# p1_apfc_and_standby.net
KiCad netlist of a schematic drawn in Altium Designer
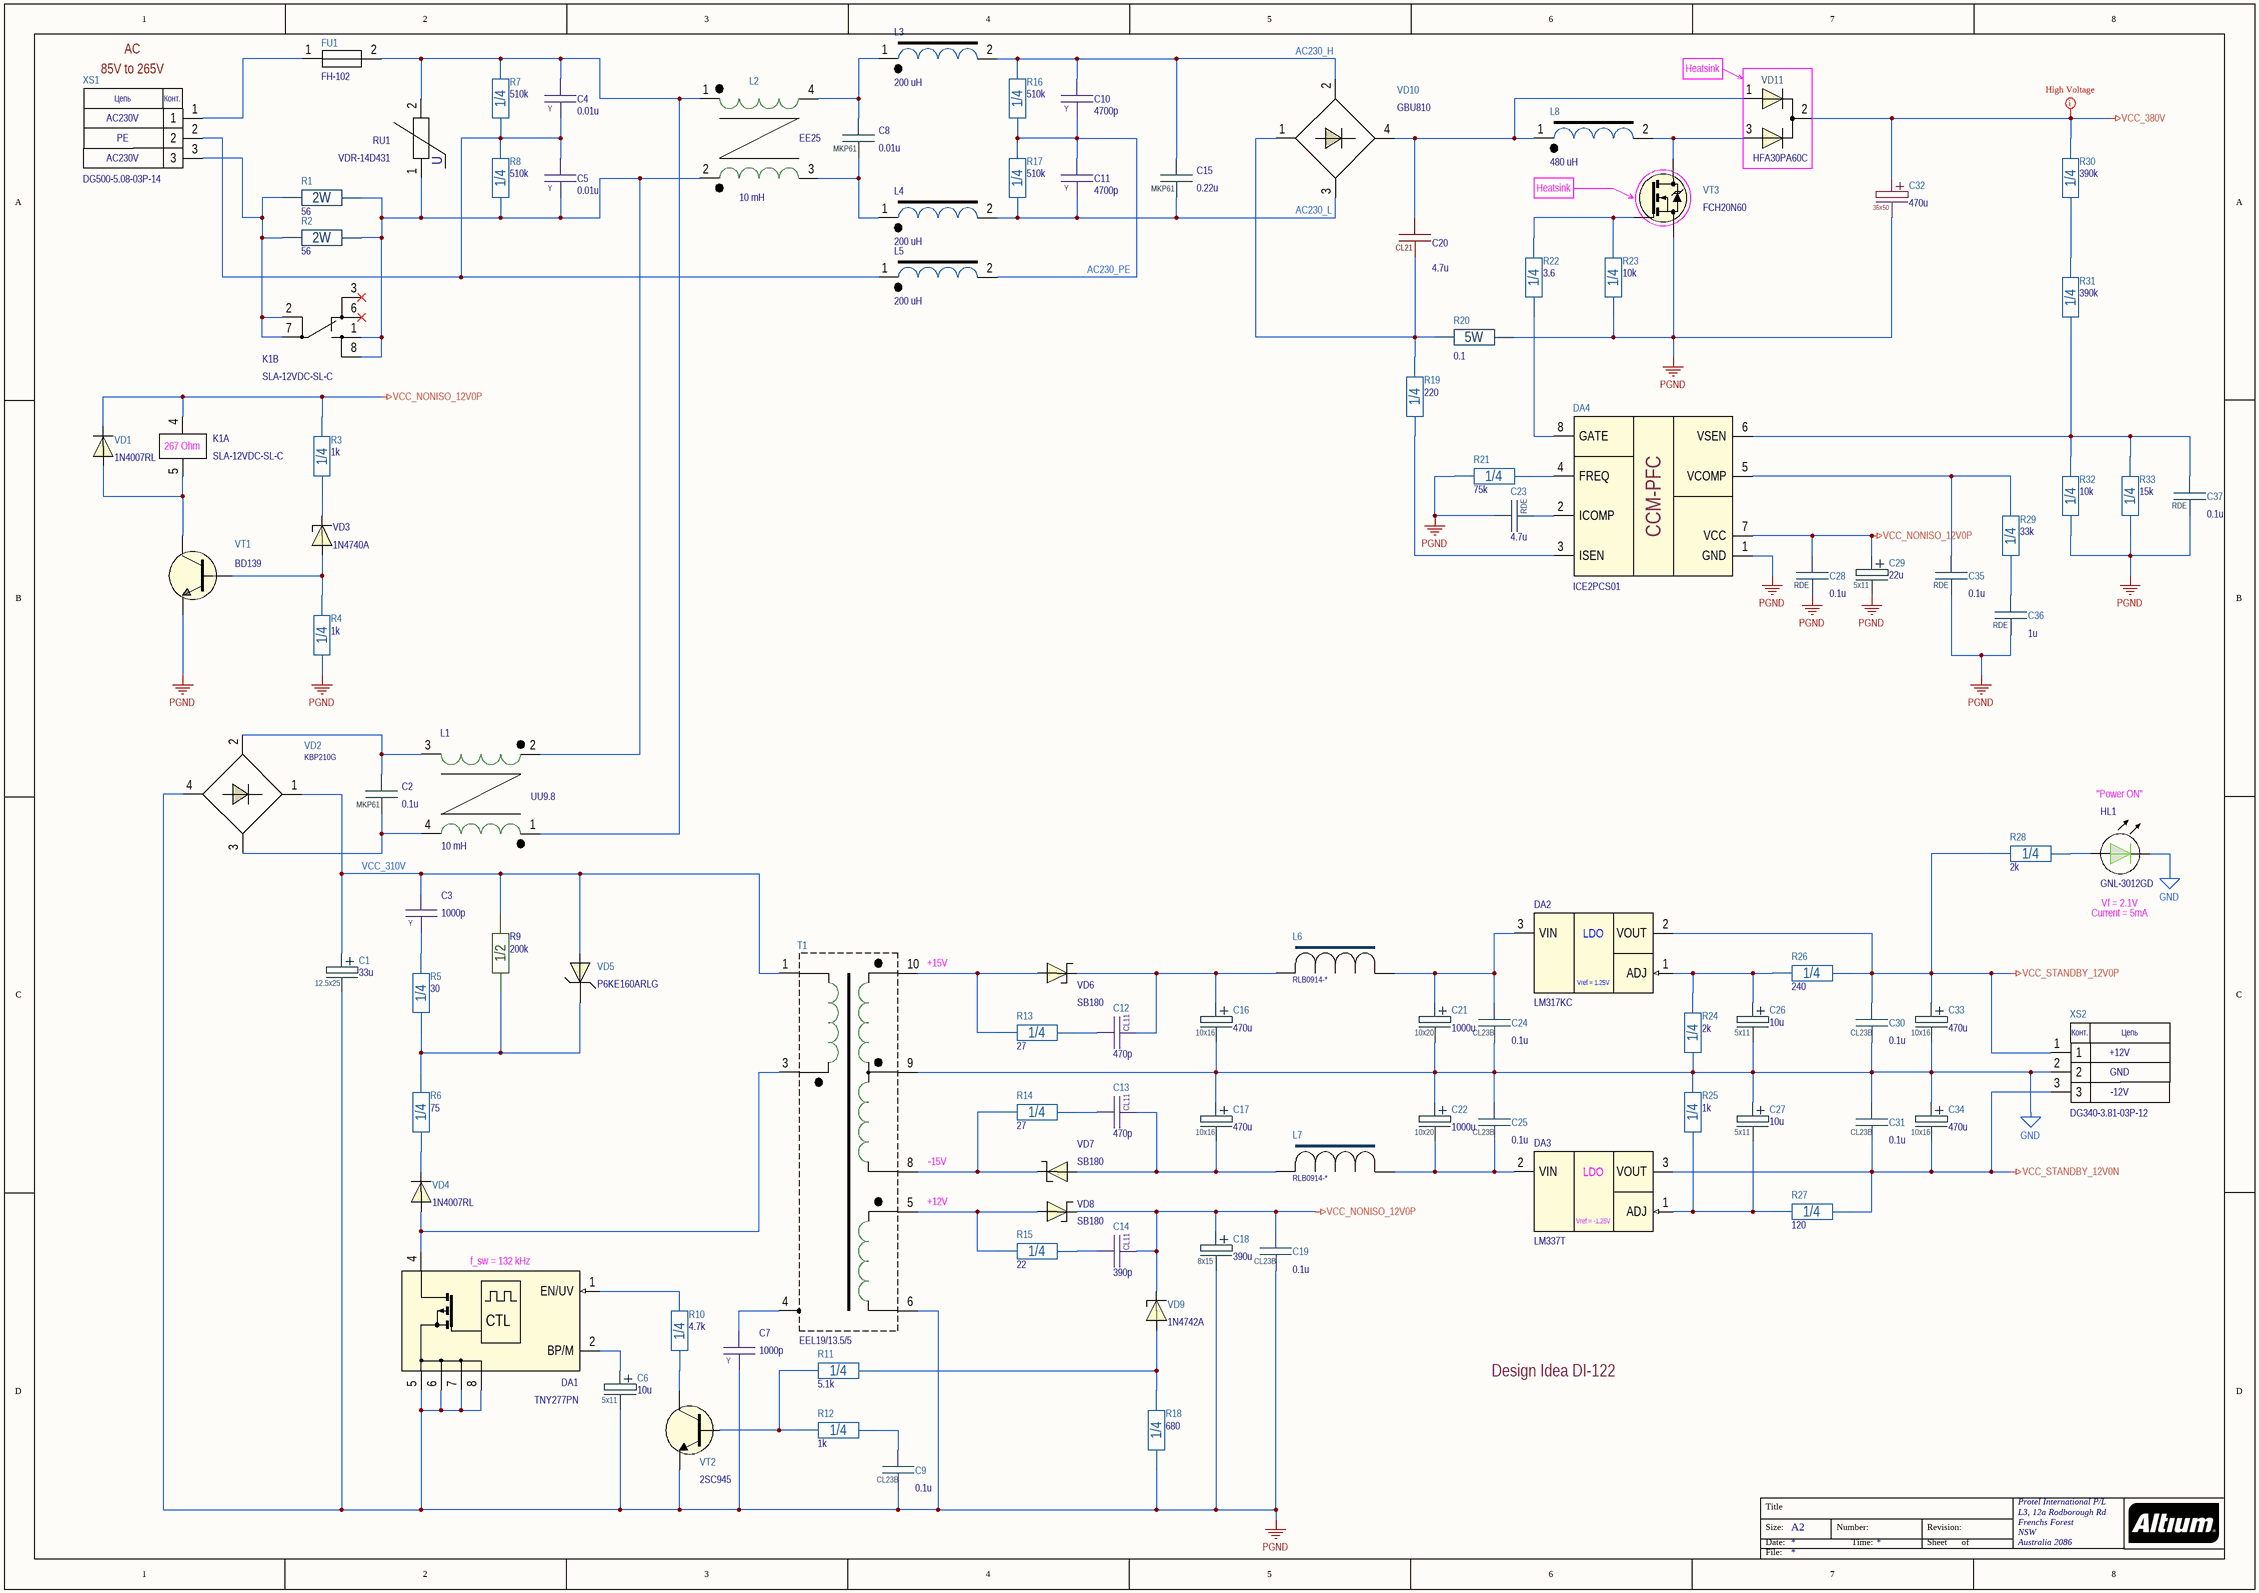
[diagram p0: p1_apfc_and_standby.SchDoc]

(export (version "E")
  (design (tool "Eeschema 10.0.6"))
  (components
    (comp (ref "C1")
      (value "33u")
      (footprint "PcbLib_RC:ECAP13X21X5_BRW")
      (description "Aluminium capacitor")
      (fields
        (field (name "TOLERANCE") "± 20 %")
        (field (name "VOLTAGE") "400V")
        (field (name "PACKAGE") "12.5x25")
      )
      (libsource (lib "Schlib_RC") (part "C_ECAP"))
    )
    (comp (ref "C2")
      (value "0.1u")
      (footprint "PcbLib_RC:MKP61_13x12x6_P10")
      (description "Metallized Polypropylene Film Capacitor for high voltage application")
      (fields
        (field (name "TOLERANCE") "± 10 %")
        (field (name "VOLTAGE") "300V")
        (field (name "PACKAGE") "MKP61")
      )
      (libsource (lib "Schlib_RC") (part "MKP61"))
    )
    (comp (ref "C3")
      (value "1000p")
      (footprint "PcbLib_RC:JYC_Y2_CAP_7.5")
      (description "High Voltage Ceramic Capacitor")
      (fields
        (field (name "TOLERANCE") "± 20 %")
        (field (name "VOLTAGE") "2000V")
        (field (name "PACKAGE") "Y")
      )
      (libsource (lib "Schlib_RC") (part "JB_Y2"))
    )
    (comp (ref "C4")
      (value "0.01u")
      (footprint "PcbLib_RC:JYC_Y2_CAP_6.5")
      (description "High Voltage Ceramic Capacitor")
      (fields
        (field (name "TOLERANCE") "± 20 %")
        (field (name "VOLTAGE") "2000V")
        (field (name "PACKAGE") "Y")
      )
      (libsource (lib "Schlib_RC") (part "JB_Y2"))
    )
    (comp (ref "C5")
      (value "0.01u")
      (footprint "PcbLib_RC:JYC_Y2_CAP_6.5")
      (description "High Voltage Ceramic Capacitor")
      (fields
        (field (name "TOLERANCE") "± 20 %")
        (field (name "VOLTAGE") "2000V")
        (field (name "PACKAGE") "Y")
      )
      (libsource (lib "Schlib_RC") (part "JB_Y2"))
    )
    (comp (ref "C6")
      (value "10u")
      (footprint "PcbLib_RC:ECAP5X11X2.0_BRW")
      (description "Aluminium capacitor")
      (fields
        (field (name "TOLERANCE") "± 20 %")
        (field (name "VOLTAGE") "63V")
        (field (name "PACKAGE") "5x11")
      )
      (libsource (lib "Schlib_RC") (part "C_ECAP"))
    )
    (comp (ref "C7")
      (value "1000p")
      (footprint "PcbLib_RC:JYC_Y2_CAP_7.5")
      (description "High Voltage Ceramic Capacitor")
      (fields
        (field (name "TOLERANCE") "± 20 %")
        (field (name "VOLTAGE") "2000V")
        (field (name "PACKAGE") "Y")
      )
      (libsource (lib "Schlib_RC") (part "JB_Y2"))
    )
    (comp (ref "C8")
      (value "0.01u")
      (footprint "PcbLib_RC:MKP61_18x12x6_P15")
      (description "Metallized Polypropylene Film Capacitor for high voltage application")
      (fields
        (field (name "TOLERANCE") "± 10 %")
        (field (name "VOLTAGE") "300V")
        (field (name "PACKAGE") "MKP61")
      )
      (libsource (lib "Schlib_RC") (part "MKP61"))
    )
    (comp (ref "C9")
      (value "0.1u")
      (footprint "PcbLib_RC:CL23B_7.2x2.5")
      (description "Box-type metallized polyester film capacitor")
      (fields
        (field (name "TOLERANCE") "± * %")
        (field (name "VOLTAGE") "63V")
        (field (name "PACKAGE") "CL23B")
      )
      (libsource (lib "Schlib_RC") (part "CL23B"))
    )
    (comp (ref "C10")
      (value "4700p")
      (footprint "PcbLib_RC:JYC_Y2_CAP_6.5")
      (description "High Voltage Ceramic Capacitor")
      (fields
        (field (name "TOLERANCE") "± 20 %")
        (field (name "VOLTAGE") "2000V")
        (field (name "PACKAGE") "Y")
      )
      (libsource (lib "Schlib_RC") (part "JB_Y2"))
    )
    (comp (ref "C11")
      (value "4700p")
      (footprint "PcbLib_RC:JYC_Y2_CAP_6.5")
      (description "High Voltage Ceramic Capacitor")
      (fields
        (field (name "TOLERANCE") "± 20 %")
        (field (name "VOLTAGE") "2000V")
        (field (name "PACKAGE") "Y")
      )
      (libsource (lib "Schlib_RC") (part "JB_Y2"))
    )
    (comp (ref "C12")
      (value "470p")
      (footprint "PcbLib_RC:CL11_6x4_P4.0")
      (description "CL11 Type Polyester Film Metal Foil Capacitor-inductive")
      (fields
        (field (name "TOLERANCE") "± 5 %")
        (field (name "VOLTAGE") "100V")
        (field (name "PACKAGE") "CL11")
      )
      (libsource (lib "Schlib_RC") (part "CL11"))
    )
    (comp (ref "C13")
      (value "470p")
      (footprint "PcbLib_RC:CL11_6x4_P4.0")
      (description "CL11 Type Polyester Film Metal Foil Capacitor-inductive")
      (fields
        (field (name "TOLERANCE") "± 5 %")
        (field (name "VOLTAGE") "100V")
        (field (name "PACKAGE") "CL11")
      )
      (libsource (lib "Schlib_RC") (part "CL11"))
    )
    (comp (ref "C14")
      (value "390p")
      (footprint "PcbLib_RC:CL11_6x4_P4.0")
      (description "CL11 Type Polyester Film Metal Foil Capacitor-inductive")
      (fields
        (field (name "TOLERANCE") "± 5 %")
        (field (name "VOLTAGE") "100V")
        (field (name "PACKAGE") "CL11")
      )
      (libsource (lib "Schlib_RC") (part "CL11"))
    )
    (comp (ref "C15")
      (value "0.22u")
      (footprint "PcbLib_RC:MKP61_18x14.5x8.5_P15")
      (description "Metallized Polypropylene Film Capacitor for high voltage application")
      (fields
        (field (name "TOLERANCE") "± 10 %")
        (field (name "VOLTAGE") "300V")
        (field (name "PACKAGE") "MKP61")
      )
      (libsource (lib "Schlib_RC") (part "MKP61"))
    )
    (comp (ref "C16")
      (value "470u")
      (footprint "PcbLib_RC:ECAP10X17X5_BRW")
      (description "Aluminium capacitor")
      (fields
        (field (name "TOLERANCE") "± 20 %")
        (field (name "VOLTAGE") "25V")
        (field (name "PACKAGE") "10x16")
      )
      (libsource (lib "Schlib_RC") (part "C_ECAP"))
    )
    (comp (ref "C17")
      (value "470u")
      (footprint "PcbLib_RC:ECAP10X17X5_BRW")
      (description "Aluminium capacitor")
      (fields
        (field (name "TOLERANCE") "± 20 %")
        (field (name "VOLTAGE") "25V")
        (field (name "PACKAGE") "10x16")
      )
      (libsource (lib "Schlib_RC") (part "C_ECAP"))
    )
    (comp (ref "C18")
      (value "390u")
      (footprint "PcbLib_RC:ECAP8X13.5X3.5_BRW")
      (description "Aluminium capacitor")
      (fields
        (field (name "TOLERANCE") "± 20 %")
        (field (name "VOLTAGE") "25V")
        (field (name "PACKAGE") "8x15")
      )
      (libsource (lib "Schlib_RC") (part "C_ECAP"))
    )
    (comp (ref "C19")
      (value "0.1u")
      (footprint "PcbLib_RC:CL23B_7.2x2.5")
      (description "Box-type metallized polyester film capacitor")
      (fields
        (field (name "TOLERANCE") "± * %")
        (field (name "VOLTAGE") "63V")
        (field (name "PACKAGE") "CL23B")
      )
      (libsource (lib "Schlib_RC") (part "CL23B"))
    )
    (comp (ref "C20")
      (value "4.7u")
      (footprint "PcbLib_RC:CL21_29x24.5x14.0_P27.5")
      (description "CL21 Type Metallized Polyester Film Capacitor")
      (fields
        (field (name "TOLERANCE") "± * %")
        (field (name "VOLTAGE") "630V")
        (field (name "PACKAGE") "CL21")
      )
      (libsource (lib "Schlib_RC") (part "CL21"))
    )
    (comp (ref "C21")
      (value "1000u")
      (footprint "PcbLib_RC:ECAP10X21X5_BRW")
      (description "Aluminium capacitor")
      (fields
        (field (name "TOLERANCE") "± 20 %")
        (field (name "VOLTAGE") "25V")
        (field (name "PACKAGE") "10x20")
      )
      (libsource (lib "Schlib_RC") (part "C_ECAP"))
    )
    (comp (ref "C22")
      (value "1000u")
      (footprint "PcbLib_RC:ECAP10X21X5_BRW")
      (description "Aluminium capacitor")
      (fields
        (field (name "TOLERANCE") "± 20 %")
        (field (name "VOLTAGE") "25V")
        (field (name "PACKAGE") "10x20")
      )
      (libsource (lib "Schlib_RC") (part "C_ECAP"))
    )
    (comp (ref "C23")
      (value "4.7u")
      (footprint "PcbLib_RC:RDE_2P1")
      (description "MLCC radial lead type with epoxy coat (RDE Series)")
      (fields
        (field (name "TOLERANCE") "± 10 %")
        (field (name "VOLTAGE") "50V")
        (field (name "PACKAGE") "RDE")
      )
      (libsource (lib "Schlib_RC") (part "RDE_CAP"))
    )
    (comp (ref "C24")
      (value "0.1u")
      (footprint "PcbLib_RC:CL23B_7.2x2.5")
      (description "Box-type metallized polyester film capacitor")
      (fields
        (field (name "TOLERANCE") "± * %")
        (field (name "VOLTAGE") "63V")
        (field (name "PACKAGE") "CL23B")
      )
      (libsource (lib "Schlib_RC") (part "CL23B"))
    )
    (comp (ref "C25")
      (value "0.1u")
      (footprint "PcbLib_RC:CL23B_7.2x2.5")
      (description "Box-type metallized polyester film capacitor")
      (fields
        (field (name "TOLERANCE") "± * %")
        (field (name "VOLTAGE") "63V")
        (field (name "PACKAGE") "CL23B")
      )
      (libsource (lib "Schlib_RC") (part "CL23B"))
    )
    (comp (ref "C26")
      (value "10u")
      (footprint "PcbLib_RC:ECAP5X11X2.0_BRW")
      (description "Aluminium capacitor")
      (fields
        (field (name "TOLERANCE") "± 20 %")
        (field (name "VOLTAGE") "63V")
        (field (name "PACKAGE") "5x11")
      )
      (libsource (lib "Schlib_RC") (part "C_ECAP"))
    )
    (comp (ref "C27")
      (value "10u")
      (footprint "PcbLib_RC:ECAP5X11X2.0_BRW")
      (description "Aluminium capacitor")
      (fields
        (field (name "TOLERANCE") "± 20 %")
        (field (name "VOLTAGE") "63V")
        (field (name "PACKAGE") "5x11")
      )
      (libsource (lib "Schlib_RC") (part "C_ECAP"))
    )
    (comp (ref "C28")
      (value "0.1u")
      (footprint "PcbLib_RC:RDE_1P1")
      (description "MLCC radial lead type with epoxy coat (RDE Series)")
      (fields
        (field (name "TOLERANCE") "± 10 %")
        (field (name "VOLTAGE") "100V")
        (field (name "PACKAGE") "RDE")
      )
      (libsource (lib "Schlib_RC") (part "RDE_CAP"))
    )
    (comp (ref "C29")
      (value "22u")
      (footprint "PcbLib_RC:ECAP5X11X2.0_BRW")
      (description "Aluminium capacitor")
      (fields
        (field (name "TOLERANCE") "± 20 %")
        (field (name "VOLTAGE") "63V")
        (field (name "PACKAGE") "5x11")
      )
      (libsource (lib "Schlib_RC") (part "C_ECAP"))
    )
    (comp (ref "C30")
      (value "0.1u")
      (footprint "PcbLib_RC:CL23B_7.2x2.5")
      (description "Box-type metallized polyester film capacitor")
      (fields
        (field (name "TOLERANCE") "± * %")
        (field (name "VOLTAGE") "63V")
        (field (name "PACKAGE") "CL23B")
      )
      (libsource (lib "Schlib_RC") (part "CL23B"))
    )
    (comp (ref "C31")
      (value "0.1u")
      (footprint "PcbLib_RC:CL23B_7.2x2.5")
      (description "Box-type metallized polyester film capacitor")
      (fields
        (field (name "TOLERANCE") "± * %")
        (field (name "VOLTAGE") "63V")
        (field (name "PACKAGE") "CL23B")
      )
      (libsource (lib "Schlib_RC") (part "CL23B"))
    )
    (comp (ref "C32")
      (value "470u")
      (footprint "PcbLib_RC:ECAP35X50X10")
      (description "Aluminium capacitors 35x50mm")
      (fields
        (field (name "TOLERANCE") "± 20 %")
        (field (name "VOLTAGE") "450V")
        (field (name "PACKAGE") "35x50")
      )
      (libsource (lib "Schlib_RC") (part "ECAP_35x50"))
    )
    (comp (ref "C33")
      (value "470u")
      (footprint "PcbLib_RC:ECAP10X17X5_BRW")
      (description "Aluminium capacitor")
      (fields
        (field (name "TOLERANCE") "± 20 %")
        (field (name "VOLTAGE") "25V")
        (field (name "PACKAGE") "10x16")
      )
      (libsource (lib "Schlib_RC") (part "C_ECAP"))
    )
    (comp (ref "C34")
      (value "470u")
      (footprint "PcbLib_RC:ECAP10X17X5_BRW")
      (description "Aluminium capacitor")
      (fields
        (field (name "TOLERANCE") "± 20 %")
        (field (name "VOLTAGE") "25V")
        (field (name "PACKAGE") "10x16")
      )
      (libsource (lib "Schlib_RC") (part "C_ECAP"))
    )
    (comp (ref "C35")
      (value "0.1u")
      (footprint "PcbLib_RC:RDE_1P1")
      (description "MLCC radial lead type with epoxy coat (RDE Series)")
      (fields
        (field (name "TOLERANCE") "± 10 %")
        (field (name "VOLTAGE") "100V")
        (field (name "PACKAGE") "RDE")
      )
      (libsource (lib "Schlib_RC") (part "RDE_CAP"))
    )
    (comp (ref "C36")
      (value "1u")
      (footprint "PcbLib_RC:RDE_2P1")
      (description "MLCC radial lead type with epoxy coat (RDE Series)")
      (fields
        (field (name "TOLERANCE") "± 10 %")
        (field (name "VOLTAGE") "50V")
        (field (name "PACKAGE") "RDE")
      )
      (libsource (lib "Schlib_RC") (part "RDE_CAP"))
    )
    (comp (ref "C37")
      (value "0.1u")
      (footprint "PcbLib_RC:RDE_1P1")
      (description "MLCC radial lead type with epoxy coat (RDE Series)")
      (fields
        (field (name "TOLERANCE") "± 10 %")
        (field (name "VOLTAGE") "100V")
        (field (name "PACKAGE") "RDE")
      )
      (libsource (lib "Schlib_RC") (part "RDE_CAP"))
    )
    (comp (ref "DA1")
      (value "TNY277PN")
      (footprint "PcbLib_ICs:DIP-8C")
      (description "Energy-Effi cient, Off-Line Switcher With Enhanced Flexibility and Extended Power Range")
      (fields (field (name "MANUFACTURER") "Power Integrations"))
      (libsource (lib "Schlib_OtherComponents") (part "TNY277PN"))
    )
    (comp (ref "DA2")
      (value "LM317KC")
      (footprint "PcbLib_ICs:TO-220A-3")
      (description "1.5 A 3-Terminal Adjustable Regulator")
      (fields (field (name "MANUFACTURER") "Texas Instruments"))
      (libsource (lib "Schlib_Texas_Instruments") (part "LM317KC"))
    )
    (comp (ref "DA3")
      (value "LM337T")
      (footprint "PcbLib_ICs:TO-220A-3")
      (description "-1.5A  3-Terminal Adjustable Negative Regulators")
      (fields (field (name "MANUFACTURER") "Texas Instruments"))
      (libsource (lib "Schlib_Texas_Instruments") (part "LM337T"))
    )
    (comp (ref "DA4")
      (value "ICE2PCS01")
      (footprint "PcbLib_ICs:DIP-8P-M01_with_SO8")
      (description "PFC Controller in Continuous Conduction Mode")
      (fields (field (name "MANUFACTURER") "International Rectifier"))
      (libsource (lib "Schlib_Infineon") (part "ICE2PCS01"))
    )
    (comp (ref "FU1")
      (value "FH-102")
      (footprint "PcbLib_Others:FH-102")
      (description "Fuse holder 5.2х20mm")
      (libsource (lib "Schlib_OtherComponents") (part "FH-102"))
    )
    (comp (ref "HL1")
      (value "GNL-3012GD")
      (footprint "PcbLib_Discrete:GNL-3012GD")
      (description "Standard Brightness 3mm LED")
      (fields (field (name "MANUFACTURER") "G-Nor Optoelectronics"))
      (libsource (lib "Schlib_OtherComponents") (part "GNL-3012GD"))
    )
    (comp (ref "K1")
      (value "SLA-12VDC-SL-C")
      (footprint "PcbLib_Others:RELAY_13x29.5MM")
      (description "Subminature high power relay 16A")
      (fields (field (name "MANUFACTURER") "Songle Relay"))
      (libsource (lib "") (part "SMIH-12VDC-SL-C_1"))
    )
    (comp (ref "L1")
      (value "10 mH")
      (footprint "PcbLib_Others:UU9.8")
      (description "UU9.8 Ferrite Core inductor")
      (fields (field (name "CORE") "UU9.8"))
      (libsource (lib "Schlib_OtherComponents") (part "UU9.8"))
    )
    (comp (ref "L2")
      (value "10 mH")
      (footprint "PcbLib_Others:EE25/10/6")
      (description "EE25 Ferrite Core inductor")
      (fields (field (name "CORE") "EE25"))
      (libsource (lib "Schlib_OtherComponents") (part "EE25"))
    )
    (comp (ref "L3")
      (value "200 uH")
      (footprint "PcbLib_RC:CORE_D20_GB")
      (description "Ferrite Core D20.3/12.7/6.35 mm")
      (libsource (lib "Schlib_OtherComponents") (part "CORE_D20"))
    )
    (comp (ref "L4")
      (value "200 uH")
      (footprint "PcbLib_RC:CORE_D20_GB")
      (description "Ferrite Core D20.3/12.7/6.35 mm")
      (libsource (lib "Schlib_OtherComponents") (part "CORE_D20"))
    )
    (comp (ref "L5")
      (value "200 uH")
      (footprint "PcbLib_RC:CORE_D20_YW")
      (description "Ferrite Core D20.3/12.7/6.35 mm")
      (libsource (lib "Schlib_OtherComponents") (part "CORE_D20"))
    )
    (comp (ref "L6")
      (value "RLB0914-*")
      (footprint "PcbLib_RC:RLB0914")
      (description "Radial Inductors")
      (fields (field (name "MANUFACTURER") "Bourns Inc."))
      (libsource (lib "Schlib_Bourns") (part "RLB0914"))
    )
    (comp (ref "L7")
      (value "RLB0914-*")
      (footprint "PcbLib_RC:RLB0914")
      (description "Radial Inductors")
      (fields (field (name "MANUFACTURER") "Bourns Inc."))
      (libsource (lib "Schlib_Bourns") (part "RLB0914"))
    )
    (comp (ref "L8")
      (value "480 uH")
      (footprint "PcbLib_RC:CORE_D36_GB")
      (description "Ferrite Core D35.8/22.4/10.5 mm")
      (libsource (lib "Schlib_OtherComponents") (part "CORE_D36"))
    )
    (comp (ref "R1")
      (value "56")
      (footprint "PcbLib_RC:CFR-200(VERTICAL)")
      (description "Resistor 2W")
      (fields
        (field (name "TOLERANCE") "± 5 %")
        (field (name "PART NUMBER") "KNP200JB-73-56R")
        (field (name "PACKAGE") "2W")
      )
      (libsource (lib "Schlib_RC") (part "CF200"))
    )
    (comp (ref "R2")
      (value "56")
      (footprint "PcbLib_RC:CFR-200(VERTICAL)")
      (description "Resistor 2W")
      (fields
        (field (name "TOLERANCE") "± 5 %")
        (field (name "PART NUMBER") "KNP200JB-73-56R")
        (field (name "PACKAGE") "2W")
      )
      (libsource (lib "Schlib_RC") (part "CF200"))
    )
    (comp (ref "R3")
      (value "1k")
      (footprint "PcbLib_RC:CFR-25")
      (description "Resistor 1/4W")
      (fields
        (field (name "TOLERANCE") "± 1 %")
        (field (name "PART NUMBER") "MFR-25FTF52-1K")
        (field (name "PACKAGE") "1/4")
      )
      (libsource (lib "Schlib_RC") (part "CF25"))
    )
    (comp (ref "R4")
      (value "1k")
      (footprint "PcbLib_RC:CFR-25")
      (description "Resistor 1/4W")
      (fields
        (field (name "TOLERANCE") "± 1 %")
        (field (name "PART NUMBER") "MFR-25FTF52-1K")
        (field (name "PACKAGE") "1/4")
      )
      (libsource (lib "Schlib_RC") (part "CF25"))
    )
    (comp (ref "R5")
      (value "30")
      (footprint "PcbLib_RC:CFR-25")
      (description "Resistor 1/4W")
      (fields
        (field (name "TOLERANCE") "± 1 %")
        (field (name "PART NUMBER") "MFR-25FTF52-30R")
        (field (name "PACKAGE") "1/4")
      )
      (libsource (lib "Schlib_RC") (part "CF25"))
    )
    (comp (ref "R6")
      (value "75")
      (footprint "PcbLib_RC:CFR-25(VERTICAL)")
      (description "Resistor 1/4W")
      (fields
        (field (name "TOLERANCE") "± 1 %")
        (field (name "PART NUMBER") "MFR-25FTF52-75R")
        (field (name "PACKAGE") "1/4")
      )
      (libsource (lib "Schlib_RC") (part "CF25"))
    )
    (comp (ref "R7")
      (value "510k")
      (footprint "PcbLib_RC:CFR-25")
      (description "Resistor 1/4W")
      (fields
        (field (name "TOLERANCE") "± 1 %")
        (field (name "PART NUMBER") "MFR-25FTF52-510K")
        (field (name "PACKAGE") "1/4")
      )
      (libsource (lib "Schlib_RC") (part "CF25"))
    )
    (comp (ref "R8")
      (value "510k")
      (footprint "PcbLib_RC:CFR-25")
      (description "Resistor 1/4W")
      (fields
        (field (name "TOLERANCE") "± 1 %")
        (field (name "PART NUMBER") "MFR-25FTF52-510K")
        (field (name "PACKAGE") "1/4")
      )
      (libsource (lib "Schlib_RC") (part "CF25"))
    )
    (comp (ref "R9")
      (value "200k")
      (footprint "PcbLib_RC:CFR-50")
      (description "Resistor 1/2W")
      (fields
        (field (name "TOLERANCE") "± 5 %")
        (field (name "PART NUMBER") "MFR-50JT-52-200K")
        (field (name "PACKAGE") "1/2")
      )
      (libsource (lib "Schlib_RC") (part "CF50"))
    )
    (comp (ref "R10")
      (value "4.7k")
      (footprint "PcbLib_RC:CFR-25")
      (description "Resistor 1/4W")
      (fields
        (field (name "TOLERANCE") "± 1 %")
        (field (name "PART NUMBER") "MFR-25FTF52-4K7")
        (field (name "PACKAGE") "1/4")
      )
      (libsource (lib "Schlib_RC") (part "CF25"))
    )
    (comp (ref "R11")
      (value "5.1k")
      (footprint "PcbLib_RC:CFR-25(VERTICAL)")
      (description "Resistor 1/4W")
      (fields
        (field (name "TOLERANCE") "± 1 %")
        (field (name "PART NUMBER") "MFR-25FTF52-5K1")
        (field (name "PACKAGE") "1/4")
      )
      (libsource (lib "Schlib_RC") (part "CF25"))
    )
    (comp (ref "R12")
      (value "1k")
      (footprint "PcbLib_RC:CFR-25")
      (description "Resistor 1/4W")
      (fields
        (field (name "TOLERANCE") "± 1 %")
        (field (name "PART NUMBER") "MFR-25FTF52-1K")
        (field (name "PACKAGE") "1/4")
      )
      (libsource (lib "Schlib_RC") (part "CF25"))
    )
    (comp (ref "R13")
      (value "27")
      (footprint "PcbLib_RC:CFR-25(VERTICAL)")
      (description "Resistor 1/4W")
      (fields
        (field (name "TOLERANCE") "± 1 %")
        (field (name "PART NUMBER") "MFR-25FTF52-27R")
        (field (name "PACKAGE") "1/4")
      )
      (libsource (lib "Schlib_RC") (part "CF25"))
    )
    (comp (ref "R14")
      (value "27")
      (footprint "PcbLib_RC:CFR-25(VERTICAL)")
      (description "Resistor 1/4W")
      (fields
        (field (name "TOLERANCE") "± 1 %")
        (field (name "PART NUMBER") "MFR-25FTF52-27R")
        (field (name "PACKAGE") "1/4")
      )
      (libsource (lib "Schlib_RC") (part "CF25"))
    )
    (comp (ref "R15")
      (value "22")
      (footprint "PcbLib_RC:CFR-25(VERTICAL)")
      (description "Resistor 1/4W")
      (fields
        (field (name "TOLERANCE") "± 1 %")
        (field (name "PART NUMBER") "MFR-25FTF52-22R")
        (field (name "PACKAGE") "1/4")
      )
      (libsource (lib "Schlib_RC") (part "CF25"))
    )
    (comp (ref "R16")
      (value "510k")
      (footprint "PcbLib_RC:CFR-25")
      (description "Resistor 1/4W")
      (fields
        (field (name "TOLERANCE") "± 1 %")
        (field (name "PART NUMBER") "MFR-25FTF52-510K")
        (field (name "PACKAGE") "1/4")
      )
      (libsource (lib "Schlib_RC") (part "CF25"))
    )
    (comp (ref "R17")
      (value "510k")
      (footprint "PcbLib_RC:CFR-25")
      (description "Resistor 1/4W")
      (fields
        (field (name "TOLERANCE") "± 1 %")
        (field (name "PART NUMBER") "MFR-25FTF52-510K")
        (field (name "PACKAGE") "1/4")
      )
      (libsource (lib "Schlib_RC") (part "CF25"))
    )
    (comp (ref "R18")
      (value "680")
      (footprint "PcbLib_RC:CFR-25")
      (description "Resistor 1/4W")
      (fields
        (field (name "TOLERANCE") "± 1 %")
        (field (name "PART NUMBER") "MFR-25FTF52-680R")
        (field (name "PACKAGE") "1/4")
      )
      (libsource (lib "Schlib_RC") (part "CF25"))
    )
    (comp (ref "R19")
      (value "220")
      (footprint "PcbLib_RC:CFR-25(VERTICAL)")
      (description "Resistor 1/4W")
      (fields
        (field (name "TOLERANCE") "± 1 %")
        (field (name "PART NUMBER") "MFR-25FTF52-220R")
        (field (name "PACKAGE") "1/4")
      )
      (libsource (lib "Schlib_RC") (part "CF25"))
    )
    (comp (ref "R20")
      (value "0.1")
      (footprint "PcbLib_RC:BPR58")
      (description "Rectangular type metal plate resistors")
      (fields
        (field (name "TOLERANCE") "± 5 %")
        (field (name "PART NUMBER") "BPR58CR10J")
        (field (name "PACKAGE") "5W")
      )
      (libsource (lib "Schlib_RC") (part "BPR58"))
    )
    (comp (ref "R21")
      (value "75k")
      (footprint "PcbLib_RC:CFR-25")
      (description "Resistor 1/4W")
      (fields
        (field (name "TOLERANCE") "± 1 %")
        (field (name "PART NUMBER") "MFR-25FTF52-75K")
        (field (name "PACKAGE") "1/4")
      )
      (libsource (lib "Schlib_RC") (part "CF25"))
    )
    (comp (ref "R22")
      (value "3.6")
      (footprint "PcbLib_RC:CFR-25(VERTICAL)")
      (description "Resistor 1/4W")
      (fields
        (field (name "TOLERANCE") "± 1 %")
        (field (name "PART NUMBER") "MFR-25FTF52-3R6")
        (field (name "PACKAGE") "1/4")
      )
      (libsource (lib "Schlib_RC") (part "CF25"))
    )
    (comp (ref "R23")
      (value "10k")
      (footprint "PcbLib_RC:CFR-25")
      (description "Resistor 1/4W")
      (fields
        (field (name "TOLERANCE") "± 1 %")
        (field (name "PART NUMBER") "MFR-25FTF52-10K")
        (field (name "PACKAGE") "1/4")
      )
      (libsource (lib "Schlib_RC") (part "CF25"))
    )
    (comp (ref "R24")
      (value "2k")
      (footprint "PcbLib_RC:CFR-25(VERTICAL)")
      (description "Resistor 1/4W")
      (fields
        (field (name "TOLERANCE") "± 1 %")
        (field (name "PART NUMBER") "MFR-25FTF52-2K")
        (field (name "PACKAGE") "1/4")
      )
      (libsource (lib "Schlib_RC") (part "CF25"))
    )
    (comp (ref "R25")
      (value "1k")
      (footprint "PcbLib_RC:CFR-25(VERTICAL)")
      (description "Resistor 1/4W")
      (fields
        (field (name "TOLERANCE") "± 1 %")
        (field (name "PART NUMBER") "MFR-25FTF52-1K")
        (field (name "PACKAGE") "1/4")
      )
      (libsource (lib "Schlib_RC") (part "CF25"))
    )
    (comp (ref "R26")
      (value "240")
      (footprint "PcbLib_RC:CFR-25(VERTICAL)")
      (description "Resistor 1/4W")
      (fields
        (field (name "TOLERANCE") "± 1 %")
        (field (name "PART NUMBER") "MFR-25FTF52-240R")
        (field (name "PACKAGE") "1/4")
      )
      (libsource (lib "Schlib_RC") (part "CF25"))
    )
    (comp (ref "R27")
      (value "120")
      (footprint "PcbLib_RC:CFR-25(VERTICAL)")
      (description "Resistor 1/4W")
      (fields
        (field (name "TOLERANCE") "± 1 %")
        (field (name "PART NUMBER") "MFR-25FTF52-120R")
        (field (name "PACKAGE") "1/4")
      )
      (libsource (lib "Schlib_RC") (part "CF25"))
    )
    (comp (ref "R28")
      (value "2k")
      (footprint "PcbLib_RC:CFR-25(VERTICAL)")
      (description "Resistor 1/4W")
      (fields
        (field (name "TOLERANCE") "± 1 %")
        (field (name "PART NUMBER") "MFR-25FTF52-2K")
        (field (name "PACKAGE") "1/4")
      )
      (libsource (lib "Schlib_RC") (part "CF25"))
    )
    (comp (ref "R29")
      (value "33k")
      (footprint "PcbLib_RC:CFR-25(VERTICAL)")
      (description "Resistor 1/4W")
      (fields
        (field (name "TOLERANCE") "± 1 %")
        (field (name "PART NUMBER") "MFR-25FTF52-33K")
        (field (name "PACKAGE") "1/4")
      )
      (libsource (lib "Schlib_RC") (part "CF25"))
    )
    (comp (ref "R30")
      (value "390k")
      (footprint "PcbLib_RC:CFR-25(VERTICAL)")
      (description "Resistor 1/4W")
      (fields
        (field (name "TOLERANCE") "± 1 %")
        (field (name "PART NUMBER") "MFR-25FTF52-390K")
        (field (name "PACKAGE") "1/4")
      )
      (libsource (lib "Schlib_RC") (part "CF25"))
    )
    (comp (ref "R31")
      (value "390k")
      (footprint "PcbLib_RC:CFR-25(VERTICAL)")
      (description "Resistor 1/4W")
      (fields
        (field (name "TOLERANCE") "± 1 %")
        (field (name "PART NUMBER") "MFR-25FTF52-390K")
        (field (name "PACKAGE") "1/4")
      )
      (libsource (lib "Schlib_RC") (part "CF25"))
    )
    (comp (ref "R32")
      (value "10k")
      (footprint "PcbLib_RC:CFR-25(VERTICAL)")
      (description "Resistor 1/4W")
      (fields
        (field (name "TOLERANCE") "± 1 %")
        (field (name "PART NUMBER") "MFR-25FTF52-10K")
        (field (name "PACKAGE") "1/4")
      )
      (libsource (lib "Schlib_RC") (part "CF25"))
    )
    (comp (ref "R33")
      (value "15k")
      (footprint "PcbLib_RC:CFR-25(VERTICAL)")
      (description "Resistor 1/4W")
      (fields
        (field (name "TOLERANCE") "± 1 %")
        (field (name "PART NUMBER") "MFR-25FTF52-15K")
        (field (name "PACKAGE") "1/4")
      )
      (libsource (lib "Schlib_RC") (part "CF25"))
    )
    (comp (ref "RU1")
      (value "VDR-14D431")
      (footprint "PcbLib_Others:VARISTOR_14D")
      (description "Varistor")
      (libsource (lib "Schlib_OtherComponents") (part "VARISTOR"))
    )
    (comp (ref "T1")
      (value "EEL19/13.5/5")
      (footprint "PcbLib_Others:EEL19/13.5/5")
      (description "EEL19 Ferrite Core, 2 output")
      (libsource (lib "Schlib_OtherComponents") (part "EEL19_V1"))
    )
    (comp (ref "VD1")
      (value "1N4007RL")
      (footprint "PcbLib_Discrete:DO-41")
      (description "1A 1000V Standard Recovery Rectifiers Diode")
      (fields (field (name "MANUFACTURER") "ON Semiconductor"))
      (libsource (lib "Schlib_ONSemiconductor") (part "1N4007RL"))
    )
    (comp (ref "VD2")
      (value "KBP210G")
      (footprint "PcbLib_Discrete:KBP210G")
      (description "2A single phase bridge rectifier")
      (fields (field (name "MANUFACTURER") "Diodes Incorporated"))
      (libsource (lib "Schlib_OtherComponents") (part "KBP210G"))
    )
    (comp (ref "VD3")
      (value "1N4740A")
      (footprint "PcbLib_Discrete:DO-41 GLASS DARK RED")
      (description "10V 1.0W ZENER DIODE")
      (fields (field (name "MANUFACTURER") "Diodes Incorporated"))
      (libsource (lib "Schlib_Diodes_Incorporated") (part "1N4740A"))
    )
    (comp (ref "VD4")
      (value "1N4007RL")
      (footprint "PcbLib_Discrete:DO-41")
      (description "1A 1000V Standard Recovery Rectifiers Diode")
      (fields (field (name "MANUFACTURER") "ON Semiconductor"))
      (libsource (lib "Schlib_ONSemiconductor") (part "1N4007RL"))
    )
    (comp (ref "VD5")
      (value "P6KE160ARLG")
      (footprint "PcbLib_Discrete:DO-15")
      (description "600 Watt Peak Power Transient\r\nVoltage Suppressors")
      (fields (field (name "MANUFACTURER") "ON Semiconductor"))
      (libsource (lib "Schlib_ONSemiconductor") (part "P6KE160ARLG"))
    )
    (comp (ref "VD6")
      (value "SB180")
      (footprint "PcbLib_Discrete:DO-41")
      (description "1A, 80V Schottky Barrier Rectifier")
      (fields (field (name "MANUFACTURER") "ON Semiconductor"))
      (libsource (lib "Schlib_ONSemiconductor") (part "SB180"))
    )
    (comp (ref "VD7")
      (value "SB180")
      (footprint "PcbLib_Discrete:DO-41")
      (description "1A, 80V Schottky Barrier Rectifier")
      (fields (field (name "MANUFACTURER") "ON Semiconductor"))
      (libsource (lib "Schlib_ONSemiconductor") (part "SB180"))
    )
    (comp (ref "VD8")
      (value "SB180")
      (footprint "PcbLib_Discrete:DO-41")
      (description "1A, 80V Schottky Barrier Rectifier")
      (fields (field (name "MANUFACTURER") "ON Semiconductor"))
      (libsource (lib "Schlib_ONSemiconductor") (part "SB180"))
    )
    (comp (ref "VD9")
      (value "1N4742A")
      (footprint "PcbLib_Discrete:DO-41 GLASS DARK RED")
      (description "12V 1.0W ZENER DIODE")
      (fields (field (name "MANUFACTURER") "Diodes Incorporated"))
      (libsource (lib "Schlib_Diodes_Incorporated") (part "1N4742A"))
    )
    (comp (ref "VD10")
      (value "GBU810")
      (footprint "PcbLib_Discrete:GBU810")
      (description "8A single phase bridge rectifier")
      (fields (field (name "MANUFACTURER") "Diodes Incorporated"))
      (libsource (lib "Schlib_OtherComponents") (part "GBU810"))
    )
    (comp (ref "VD11")
      (value "HFA30PA60C")
      (footprint "PcbLib_ICs:TO-247_with_dual_TO-220")
      (description "Ultrafast, Soft Recovery Diode 600V, 15A")
      (fields (field (name "MANUFACTURER") "Infineon"))
      (libsource (lib "Schlib_Infineon") (part "HFA30PA60C"))
    )
    (comp (ref "VT1")
      (value "BD139")
      (footprint "PcbLib_ICs:TO-126 (VERTICAL)")
      (description "General Purpose n-p-n Transistors")
      (fields (field (name "MANUFACTURER") "STMicroelectronics"))
      (libsource (lib "Schlib_STMicroelectronics") (part "BD139"))
    )
    (comp (ref "VT2")
      (value "2SC945")
      (footprint "PcbLib_ICs:TO-92 (VERTICAL,LINE)")
      (description "General Purpose n-p-n Transistors")
      (fields (field (name "MANUFACTURER") "NEC"))
      (libsource (lib "Schlib_NEC") (part "2SC945"))
    )
    (comp (ref "VT3")
      (value "FCH20N60")
      (footprint "PcbLib_ICs:TO-247_with_TO-220 (VERTICAL)")
      (description "600V @ 20A N-Channel MOSFET")
      (fields (field (name "MANUFACTURER") "ON Semiconductor"))
      (libsource (lib "Schlib_ONSemiconductor") (part "FCH20N60"))
    )
    (comp (ref "XS1")
      (value "DG500-5.08-03P-14")
      (footprint "PcbLib_Connectors:DG500-5.08-03P")
      (description "3-way screw terminal, pitch 200mils (5.08mm)")
      (fields (field (name "MANUFACTURER") "DEGSON"))
      (libsource (lib "Schlib_OtherComponents") (part "DG500-5.08-03P-14"))
    )
    (comp (ref "XS2")
      (value "DG340-3.81-03P-12")
      (footprint "PcbLib_Connectors:DG340-3.81-03P")
      (description "3-way screw terminal, pitch 150mils (3.81mm)")
      (fields (field (name "MANUFACTURER") "DEGSON"))
      (libsource (lib "Schlib_OtherComponents") (part "DG340-3.81-03P-12"))
    )
  )
  (nets
    (net (code "1") (name "/AC230_H") (class "Default")
      (node (ref "C10") (pin "1") (pinfunction "1_1") (pintype "passive"))
      (node (ref "C15") (pin "2") (pinfunction "2_2") (pintype "passive"))
      (node (ref "L3") (pin "2") (pinfunction "2_2") (pintype "passive"))
      (node (ref "R16") (pin "2") (pinfunction "2_2") (pintype "passive"))
      (node (ref "VD10") (pin "2") (pinfunction "AC1_2") (pintype "passive"))
    )
    (net (code "2") (name "/AC230_L") (class "Default")
      (node (ref "C11") (pin "2") (pinfunction "2_2") (pintype "passive"))
      (node (ref "C15") (pin "1") (pinfunction "1_1") (pintype "passive"))
      (node (ref "L4") (pin "2") (pinfunction "2_2") (pintype "passive"))
      (node (ref "R17") (pin "1") (pinfunction "1_1") (pintype "passive"))
      (node (ref "VD10") (pin "3") (pinfunction "AC2_3") (pintype "passive"))
    )
    (net (code "3") (name "/AC230_PE") (class "Default")
      (node (ref "C10") (pin "2") (pinfunction "2_2") (pintype "passive"))
      (node (ref "C11") (pin "1") (pinfunction "1_1") (pintype "passive"))
      (node (ref "L5") (pin "2") (pinfunction "2_2") (pintype "passive"))
      (node (ref "R16") (pin "1") (pinfunction "1_1") (pintype "passive"))
      (node (ref "R17") (pin "2") (pinfunction "2_2") (pintype "passive"))
    )
    (net (code "4") (name "/VCC_310V") (class "Default")
      (node (ref "C1") (pin "1") (pinfunction "1_1") (pintype "passive"))
      (node (ref "C3") (pin "2") (pinfunction "2_2") (pintype "passive"))
      (node (ref "R9") (pin "2") (pinfunction "2_2") (pintype "passive"))
      (node (ref "T1") (pin "1") (pinfunction "1_1") (pintype "passive"))
      (node (ref "VD2") (pin "1") (pinfunction "M_1") (pintype "passive"))
      (node (ref "VD5") (pin "2") (pinfunction "A_2") (pintype "passive"))
    )
    (net (code "5") (name "GND") (class "Default")
      (node (ref "C16") (pin "2") (pinfunction "2_2") (pintype "passive"))
      (node (ref "C17") (pin "1") (pinfunction "1_1") (pintype "passive"))
      (node (ref "C21") (pin "2") (pinfunction "2_2") (pintype "passive"))
      (node (ref "C22") (pin "1") (pinfunction "1_1") (pintype "passive"))
      (node (ref "C24") (pin "2") (pinfunction "2_2") (pintype "passive"))
      (node (ref "C25") (pin "1") (pinfunction "1_1") (pintype "passive"))
      (node (ref "C26") (pin "2") (pinfunction "2_2") (pintype "passive"))
      (node (ref "C27") (pin "1") (pinfunction "1_1") (pintype "passive"))
      (node (ref "C30") (pin "2") (pinfunction "2_2") (pintype "passive"))
      (node (ref "C31") (pin "1") (pinfunction "1_1") (pintype "passive"))
      (node (ref "C33") (pin "2") (pinfunction "2_2") (pintype "passive"))
      (node (ref "C34") (pin "1") (pinfunction "1_1") (pintype "passive"))
      (node (ref "HL1") (pin "1") (pinfunction "1_1") (pintype "passive"))
      (node (ref "R24") (pin "1") (pinfunction "1_1") (pintype "passive"))
      (node (ref "R25") (pin "2") (pinfunction "2_2") (pintype "passive"))
      (node (ref "T1") (pin "9") (pinfunction "9_9") (pintype "passive"))
      (node (ref "XS2") (pin "2") (pinfunction "2_2") (pintype "passive"))
    )
    (net (code "6") (name "Net-(C3-Pad1)") (class "Default")
      (node (ref "C3") (pin "1") (pinfunction "1_1") (pintype "passive"))
      (node (ref "R5") (pin "1") (pinfunction "1_1") (pintype "passive"))
    )
    (net (code "7") (name "Net-(C4-Pad1)") (class "Default")
      (node (ref "C4") (pin "1") (pinfunction "1_1") (pintype "passive"))
      (node (ref "FU1") (pin "2") (pinfunction "2_2") (pintype "passive"))
      (node (ref "L1") (pin "1") (pinfunction "1_1") (pintype "passive"))
      (node (ref "L2") (pin "1") (pinfunction "1_1") (pintype "passive"))
      (node (ref "R7") (pin "2") (pinfunction "2_2") (pintype "passive"))
      (node (ref "RU1") (pin "2") (pinfunction "2_2") (pintype "passive"))
    )
    (net (code "8") (name "Net-(C4-Pad2)") (class "Default")
      (node (ref "C4") (pin "2") (pinfunction "2_2") (pintype "passive"))
      (node (ref "C5") (pin "1") (pinfunction "1_1") (pintype "passive"))
      (node (ref "L5") (pin "1") (pinfunction "1_1") (pintype "passive"))
      (node (ref "R7") (pin "1") (pinfunction "1_1") (pintype "passive"))
      (node (ref "R8") (pin "2") (pinfunction "2_2") (pintype "passive"))
      (node (ref "XS1") (pin "2") (pinfunction "2_2") (pintype "passive"))
    )
    (net (code "9") (name "Net-(C5-Pad2)") (class "Default")
      (node (ref "C5") (pin "2") (pinfunction "2_2") (pintype "passive"))
      (node (ref "K1") (pin "1") (pinfunction "1_1") (pintype "passive"))
      (node (ref "K1") (pin "8") (pinfunction "8_8") (pintype "passive"))
      (node (ref "L1") (pin "2") (pinfunction "2_2") (pintype "passive"))
      (node (ref "L2") (pin "2") (pinfunction "2_2") (pintype "passive"))
      (node (ref "R1") (pin "1") (pinfunction "1_1") (pintype "passive"))
      (node (ref "R2") (pin "1") (pinfunction "1_1") (pintype "passive"))
      (node (ref "R8") (pin "1") (pinfunction "1_1") (pintype "passive"))
      (node (ref "RU1") (pin "1") (pinfunction "1_1") (pintype "passive"))
    )
    (net (code "10") (name "Net-(C7-Pad2)") (class "Default")
      (node (ref "C7") (pin "2") (pinfunction "2_2") (pintype "passive"))
      (node (ref "T1") (pin "4") (pinfunction "4_4") (pintype "passive"))
    )
    (net (code "11") (name "Net-(C8-Pad1)") (class "Default")
      (node (ref "C8") (pin "1") (pinfunction "1_1") (pintype "passive"))
      (node (ref "L2") (pin "3") (pinfunction "3_3") (pintype "passive"))
      (node (ref "L4") (pin "1") (pinfunction "1_1") (pintype "passive"))
    )
    (net (code "12") (name "Net-(C8-Pad2)") (class "Default")
      (node (ref "C8") (pin "2") (pinfunction "2_2") (pintype "passive"))
      (node (ref "L2") (pin "4") (pinfunction "4_4") (pintype "passive"))
      (node (ref "L3") (pin "1") (pinfunction "1_1") (pintype "passive"))
    )
    (net (code "13") (name "Net-(C9-Pad1)") (class "Default")
      (node (ref "C9") (pin "1") (pinfunction "1_1") (pintype "passive"))
      (node (ref "R12") (pin "2") (pinfunction "2_2") (pintype "passive"))
    )
    (net (code "14") (name "Net-(C12-Pad2)") (class "Default")
      (node (ref "C12") (pin "2") (pinfunction "2_2") (pintype "passive"))
      (node (ref "R13") (pin "1") (pinfunction "1_1") (pintype "passive"))
    )
    (net (code "15") (name "Net-(C13-Pad2)") (class "Default")
      (node (ref "C13") (pin "2") (pinfunction "2_2") (pintype "passive"))
      (node (ref "R14") (pin "1") (pinfunction "1_1") (pintype "passive"))
    )
    (net (code "16") (name "Net-(C14-Pad2)") (class "Default")
      (node (ref "C14") (pin "2") (pinfunction "2_2") (pintype "passive"))
      (node (ref "R15") (pin "1") (pinfunction "1_1") (pintype "passive"))
    )
    (net (code "17") (name "Net-(C36-Pad1)") (class "Default")
      (node (ref "C36") (pin "1") (pinfunction "1_1") (pintype "passive"))
      (node (ref "R29") (pin "1") (pinfunction "1_1") (pintype "passive"))
    )
    (net (code "18") (name "Net-(DA1-BP{slash}M)") (class "Default")
      (node (ref "C6") (pin "1") (pinfunction "1_1") (pintype "passive"))
      (node (ref "DA1") (pin "2") (pinfunction "BP/M_2") (pintype "passive"))
    )
    (net (code "19") (name "Net-(DA1-DRAIN)") (class "Default")
      (node (ref "DA1") (pin "4") (pinfunction "DRAIN_4") (pintype "passive"))
      (node (ref "T1") (pin "3") (pinfunction "3_3") (pintype "passive"))
      (node (ref "VD4") (pin "2") (pinfunction "A_2") (pintype "passive"))
    )
    (net (code "20") (name "Net-(DA1-EN{slash}UV)") (class "Default")
      (node (ref "DA1") (pin "1") (pinfunction "EN/UV_1") (pintype "input"))
      (node (ref "R10") (pin "1") (pinfunction "1_1") (pintype "passive"))
    )
    (net (code "21") (name "Net-(DA2-ADJ)") (class "Default")
      (node (ref "C26") (pin "1") (pinfunction "1_1") (pintype "passive"))
      (node (ref "DA2") (pin "1") (pinfunction "ADJ_1") (pintype "input"))
      (node (ref "R24") (pin "2") (pinfunction "2_2") (pintype "passive"))
      (node (ref "R26") (pin "2") (pinfunction "2_2") (pintype "passive"))
    )
    (net (code "22") (name "Net-(DA2-VIN)") (class "Default")
      (node (ref "C21") (pin "1") (pinfunction "1_1") (pintype "passive"))
      (node (ref "C24") (pin "1") (pinfunction "1_1") (pintype "passive"))
      (node (ref "DA2") (pin "3") (pinfunction "VIN_3") (pintype "power_in"))
      (node (ref "L6") (pin "2") (pinfunction "2_2") (pintype "passive"))
    )
    (net (code "23") (name "Net-(DA3-ADJ)") (class "Default")
      (node (ref "C27") (pin "2") (pinfunction "2_2") (pintype "passive"))
      (node (ref "DA3") (pin "1") (pinfunction "ADJ_1") (pintype "input"))
      (node (ref "R25") (pin "1") (pinfunction "1_1") (pintype "passive"))
      (node (ref "R27") (pin "2") (pinfunction "2_2") (pintype "passive"))
    )
    (net (code "24") (name "Net-(DA3-VIN)") (class "Default")
      (node (ref "C22") (pin "2") (pinfunction "2_2") (pintype "passive"))
      (node (ref "C25") (pin "2") (pinfunction "2_2") (pintype "passive"))
      (node (ref "DA3") (pin "2") (pinfunction "VIN_2") (pintype "power_in"))
      (node (ref "L7") (pin "2") (pinfunction "2_2") (pintype "passive"))
    )
    (net (code "25") (name "Net-(DA4-FREQ)") (class "Default")
      (node (ref "DA4") (pin "4") (pinfunction "FREQ_4") (pintype "passive"))
      (node (ref "R21") (pin "1") (pinfunction "1_1") (pintype "passive"))
    )
    (net (code "26") (name "Net-(DA4-GATE)") (class "Default")
      (node (ref "DA4") (pin "8") (pinfunction "GATE_8") (pintype "passive"))
      (node (ref "R22") (pin "1") (pinfunction "1_1") (pintype "passive"))
    )
    (net (code "27") (name "Net-(DA4-ICOMP)") (class "Default")
      (node (ref "C23") (pin "2") (pinfunction "2_2") (pintype "passive"))
      (node (ref "DA4") (pin "2") (pinfunction "ICOMP_2") (pintype "passive"))
    )
    (net (code "28") (name "Net-(DA4-ISEN)") (class "Default")
      (node (ref "DA4") (pin "3") (pinfunction "ISEN_3") (pintype "passive"))
      (node (ref "R19") (pin "1") (pinfunction "1_1") (pintype "passive"))
    )
    (net (code "29") (name "Net-(DA4-VCOMP)") (class "Default")
      (node (ref "C35") (pin "1") (pinfunction "1_1") (pintype "passive"))
      (node (ref "DA4") (pin "5") (pinfunction "VCOMP_5") (pintype "passive"))
      (node (ref "R29") (pin "2") (pinfunction "2_2") (pintype "passive"))
    )
    (net (code "30") (name "Net-(DA4-VSEN)") (class "Default")
      (node (ref "C37") (pin "1") (pinfunction "1_1") (pintype "passive"))
      (node (ref "DA4") (pin "6") (pinfunction "VSEN_6") (pintype "passive"))
      (node (ref "R31") (pin "1") (pinfunction "1_1") (pintype "passive"))
      (node (ref "R32") (pin "1") (pinfunction "1_1") (pintype "passive"))
      (node (ref "R33") (pin "2") (pinfunction "2_2") (pintype "passive"))
    )
    (net (code "31") (name "Net-(FU1-Pad1)") (class "Default")
      (node (ref "FU1") (pin "1") (pinfunction "1_1") (pintype "passive"))
      (node (ref "XS1") (pin "1") (pinfunction "1_1") (pintype "passive"))
    )
    (net (code "32") (name "Net-(HL1-Pad2)") (class "Default")
      (node (ref "HL1") (pin "2") (pinfunction "2_2") (pintype "passive"))
      (node (ref "R28") (pin "1") (pinfunction "1_1") (pintype "passive"))
    )
    (net (code "33") (name "Net-(K1-Pad2)") (class "Default")
      (node (ref "K1") (pin "2") (pinfunction "2_2") (pintype "passive"))
      (node (ref "K1") (pin "7") (pinfunction "7_7") (pintype "passive"))
      (node (ref "R1") (pin "2") (pinfunction "2_2") (pintype "passive"))
      (node (ref "R2") (pin "2") (pinfunction "2_2") (pintype "passive"))
      (node (ref "XS1") (pin "3") (pinfunction "3_3") (pintype "passive"))
    )
    (net (code "34") (name "Net-(R30-Pad1)") (class "Default")
      (node (ref "R30") (pin "1") (pinfunction "1_1") (pintype "passive"))
      (node (ref "R31") (pin "2") (pinfunction "2_2") (pintype "passive"))
    )
    (net (code "35") (name "Net-(VD1-A)") (class "Default")
      (node (ref "K1") (pin "5") (pinfunction "5_5") (pintype "passive"))
      (node (ref "VD1") (pin "2") (pinfunction "A_2") (pintype "passive"))
      (node (ref "VT1") (pin "2") (pinfunction "C_2") (pintype "passive"))
    )
    (net (code "36") (name "Net-(VD2-AC1)") (class "Default")
      (node (ref "C2") (pin "2") (pinfunction "2_2") (pintype "passive"))
      (node (ref "L1") (pin "3") (pinfunction "3_3") (pintype "passive"))
      (node (ref "VD2") (pin "2") (pinfunction "AC1_2") (pintype "passive"))
    )
    (net (code "37") (name "Net-(VD2-AC2)") (class "Default")
      (node (ref "C2") (pin "1") (pinfunction "1_1") (pintype "passive"))
      (node (ref "L1") (pin "4") (pinfunction "4_4") (pintype "passive"))
      (node (ref "VD2") (pin "3") (pinfunction "AC2_3") (pintype "passive"))
    )
    (net (code "38") (name "Net-(VD3-ANODE)") (class "Default")
      (node (ref "R4") (pin "2") (pinfunction "2_2") (pintype "passive"))
      (node (ref "VD3") (pin "2") (pinfunction "ANODE_2") (pintype "power_in"))
      (node (ref "VT1") (pin "1") (pinfunction "B_1") (pintype "passive"))
    )
    (net (code "39") (name "Net-(VD3-CATHODE)") (class "Default")
      (node (ref "R3") (pin "1") (pinfunction "1_1") (pintype "passive"))
      (node (ref "VD3") (pin "1") (pinfunction "CATHODE_1") (pintype "passive"))
    )
    (net (code "40") (name "Net-(VD4-C)") (class "Default")
      (node (ref "R6") (pin "2") (pinfunction "2_2") (pintype "passive"))
      (node (ref "VD4") (pin "1") (pinfunction "C_1") (pintype "passive"))
    )
    (net (code "41") (name "Net-(VD5-C)") (class "Default")
      (node (ref "R5") (pin "2") (pinfunction "2_2") (pintype "passive"))
      (node (ref "R6") (pin "1") (pinfunction "1_1") (pintype "passive"))
      (node (ref "R9") (pin "1") (pinfunction "1_1") (pintype "passive"))
      (node (ref "VD5") (pin "1") (pinfunction "C_1") (pintype "passive"))
    )
    (net (code "42") (name "Net-(VD6-A)") (class "Default")
      (node (ref "R13") (pin "2") (pinfunction "2_2") (pintype "passive"))
      (node (ref "T1") (pin "10") (pinfunction "10_10") (pintype "passive"))
      (node (ref "VD6") (pin "2") (pinfunction "A_2") (pintype "passive"))
    )
    (net (code "43") (name "Net-(VD6-C)") (class "Default")
      (node (ref "C12") (pin "1") (pinfunction "1_1") (pintype "passive"))
      (node (ref "C16") (pin "1") (pinfunction "1_1") (pintype "passive"))
      (node (ref "L6") (pin "1") (pinfunction "1_1") (pintype "passive"))
      (node (ref "VD6") (pin "1") (pinfunction "C_1") (pintype "passive"))
    )
    (net (code "44") (name "Net-(VD7-A)") (class "Default")
      (node (ref "C13") (pin "1") (pinfunction "1_1") (pintype "passive"))
      (node (ref "C17") (pin "2") (pinfunction "2_2") (pintype "passive"))
      (node (ref "L7") (pin "1") (pinfunction "1_1") (pintype "passive"))
      (node (ref "VD7") (pin "2") (pinfunction "A_2") (pintype "passive"))
    )
    (net (code "45") (name "Net-(VD7-C)") (class "Default")
      (node (ref "R14") (pin "2") (pinfunction "2_2") (pintype "passive"))
      (node (ref "T1") (pin "8") (pinfunction "8_8") (pintype "passive"))
      (node (ref "VD7") (pin "1") (pinfunction "C_1") (pintype "passive"))
    )
    (net (code "46") (name "Net-(VD8-A)") (class "Default")
      (node (ref "R15") (pin "2") (pinfunction "2_2") (pintype "passive"))
      (node (ref "T1") (pin "5") (pinfunction "5_5") (pintype "passive"))
      (node (ref "VD8") (pin "2") (pinfunction "A_2") (pintype "passive"))
    )
    (net (code "47") (name "Net-(VD9-ANODE)") (class "Default")
      (node (ref "R11") (pin "1") (pinfunction "1_1") (pintype "passive"))
      (node (ref "R18") (pin "1") (pinfunction "1_1") (pintype "passive"))
      (node (ref "VD9") (pin "2") (pinfunction "ANODE_2") (pintype "power_in"))
    )
    (net (code "48") (name "Net-(VD10-M)") (class "Default")
      (node (ref "C20") (pin "1") (pinfunction "1_1") (pintype "passive"))
      (node (ref "R19") (pin "2") (pinfunction "2_2") (pintype "passive"))
      (node (ref "R20") (pin "1") (pinfunction "1_1") (pintype "passive"))
      (node (ref "VD10") (pin "1") (pinfunction "M_1") (pintype "passive"))
    )
    (net (code "49") (name "Net-(VD10-P)") (class "Default")
      (node (ref "C20") (pin "2") (pinfunction "2_2") (pintype "passive"))
      (node (ref "L8") (pin "1") (pinfunction "1_1") (pintype "passive"))
      (node (ref "VD10") (pin "4") (pinfunction "P_4") (pintype "passive"))
      (node (ref "VD11") (pin "1") (pinfunction "A1_1") (pintype "passive"))
    )
    (net (code "50") (name "Net-(VD11-A2)") (class "Default")
      (node (ref "L8") (pin "2") (pinfunction "2_2") (pintype "passive"))
      (node (ref "VD11") (pin "3") (pinfunction "A2_3") (pintype "passive"))
      (node (ref "VT3") (pin "2") (pinfunction "D_2") (pintype "passive"))
    )
    (net (code "51") (name "Net-(VT2-B)") (class "Default")
      (node (ref "R11") (pin "2") (pinfunction "2_2") (pintype "passive"))
      (node (ref "R12") (pin "1") (pinfunction "1_1") (pintype "passive"))
      (node (ref "VT2") (pin "1") (pinfunction "B_1") (pintype "passive"))
    )
    (net (code "52") (name "Net-(VT2-C)") (class "Default")
      (node (ref "R10") (pin "2") (pinfunction "2_2") (pintype "passive"))
      (node (ref "VT2") (pin "2") (pinfunction "C_2") (pintype "passive"))
    )
    (net (code "53") (name "Net-(VT3-G)") (class "Default")
      (node (ref "R22") (pin "2") (pinfunction "2_2") (pintype "passive"))
      (node (ref "R23") (pin "2") (pinfunction "2_2") (pintype "passive"))
      (node (ref "VT3") (pin "1") (pinfunction "G_1") (pintype "passive"))
    )
    (net (code "54") (name "PGND") (class "Default")
      (node (ref "C1") (pin "2") (pinfunction "2_2") (pintype "passive"))
      (node (ref "C18") (pin "2") (pinfunction "2_2") (pintype "passive"))
      (node (ref "C19") (pin "2") (pinfunction "2_2") (pintype "passive"))
      (node (ref "C23") (pin "1") (pinfunction "1_1") (pintype "passive"))
      (node (ref "C28") (pin "2") (pinfunction "2_2") (pintype "passive"))
      (node (ref "C29") (pin "2") (pinfunction "2_2") (pintype "passive"))
      (node (ref "C32") (pin "2") (pinfunction "2_2") (pintype "passive"))
      (node (ref "C35") (pin "2") (pinfunction "2_2") (pintype "passive"))
      (node (ref "C36") (pin "2") (pinfunction "2_2") (pintype "passive"))
      (node (ref "C37") (pin "2") (pinfunction "2_2") (pintype "passive"))
      (node (ref "C6") (pin "2") (pinfunction "2_2") (pintype "passive"))
      (node (ref "C7") (pin "1") (pinfunction "1_1") (pintype "passive"))
      (node (ref "C9") (pin "2") (pinfunction "2_2") (pintype "passive"))
      (node (ref "DA1") (pin "5") (pinfunction "SOURCE_5") (pintype "passive"))
      (node (ref "DA1") (pin "6") (pinfunction "SOURCE_6") (pintype "passive"))
      (node (ref "DA1") (pin "7") (pinfunction "SOURCE_7") (pintype "passive"))
      (node (ref "DA1") (pin "8") (pinfunction "SOURCE_8") (pintype "passive"))
      (node (ref "DA4") (pin "1") (pinfunction "GND_1") (pintype "passive"))
      (node (ref "R18") (pin "2") (pinfunction "2_2") (pintype "passive"))
      (node (ref "R20") (pin "2") (pinfunction "2_2") (pintype "passive"))
      (node (ref "R21") (pin "2") (pinfunction "2_2") (pintype "passive"))
      (node (ref "R23") (pin "1") (pinfunction "1_1") (pintype "passive"))
      (node (ref "R32") (pin "2") (pinfunction "2_2") (pintype "passive"))
      (node (ref "R33") (pin "1") (pinfunction "1_1") (pintype "passive"))
      (node (ref "R4") (pin "1") (pinfunction "1_1") (pintype "passive"))
      (node (ref "T1") (pin "6") (pinfunction "6_6") (pintype "passive"))
      (node (ref "VD2") (pin "4") (pinfunction "P_4") (pintype "passive"))
      (node (ref "VT1") (pin "3") (pinfunction "E_3") (pintype "passive"))
      (node (ref "VT2") (pin "3") (pinfunction "E_3") (pintype "passive"))
      (node (ref "VT3") (pin "3") (pinfunction "S_3") (pintype "passive"))
    )
    (net (code "55") (name "VCC_380V") (class "Default")
      (node (ref "C32") (pin "1") (pinfunction "1_1") (pintype "passive"))
      (node (ref "R30") (pin "2") (pinfunction "2_2") (pintype "passive"))
      (node (ref "VD11") (pin "2") (pinfunction "C_2") (pintype "passive"))
    )
    (net (code "56") (name "VCC_NONISO_12V0P") (class "Default")
      (node (ref "C14") (pin "1") (pinfunction "1_1") (pintype "passive"))
      (node (ref "C18") (pin "1") (pinfunction "1_1") (pintype "passive"))
      (node (ref "C19") (pin "1") (pinfunction "1_1") (pintype "passive"))
      (node (ref "C28") (pin "1") (pinfunction "1_1") (pintype "passive"))
      (node (ref "C29") (pin "1") (pinfunction "1_1") (pintype "passive"))
      (node (ref "DA4") (pin "7") (pinfunction "VCC_7") (pintype "passive"))
      (node (ref "K1") (pin "4") (pinfunction "4_4") (pintype "passive"))
      (node (ref "R3") (pin "2") (pinfunction "2_2") (pintype "passive"))
      (node (ref "VD1") (pin "1") (pinfunction "C_1") (pintype "passive"))
      (node (ref "VD8") (pin "1") (pinfunction "C_1") (pintype "passive"))
      (node (ref "VD9") (pin "1") (pinfunction "CATHODE_1") (pintype "passive"))
    )
    (net (code "57") (name "VCC_STANDBY_12V0N") (class "Default")
      (node (ref "C31") (pin "2") (pinfunction "2_2") (pintype "passive"))
      (node (ref "C34") (pin "2") (pinfunction "2_2") (pintype "passive"))
      (node (ref "DA3") (pin "3") (pinfunction "VOUT_3") (pintype "power_in"))
      (node (ref "R27") (pin "1") (pinfunction "1_1") (pintype "passive"))
      (node (ref "XS2") (pin "3") (pinfunction "3_3") (pintype "passive"))
    )
    (net (code "58") (name "VCC_STANDBY_12V0P") (class "Default")
      (node (ref "C30") (pin "1") (pinfunction "1_1") (pintype "passive"))
      (node (ref "C33") (pin "1") (pinfunction "1_1") (pintype "passive"))
      (node (ref "DA2") (pin "2") (pinfunction "VOUT_2") (pintype "power_in"))
      (node (ref "R26") (pin "1") (pinfunction "1_1") (pintype "passive"))
      (node (ref "R28") (pin "2") (pinfunction "2_2") (pintype "passive"))
      (node (ref "XS2") (pin "1") (pinfunction "1_1") (pintype "passive"))
    )
    (net (code "59") (name "unconnected-(K1-Pad3)") (class "Default")
      (node (ref "K1") (pin "3") (pinfunction "3_3") (pintype "passive+no_connect"))
    )
    (net (code "60") (name "unconnected-(K1-Pad6)") (class "Default")
      (node (ref "K1") (pin "6") (pinfunction "6_6") (pintype "passive+no_connect"))
    )
  )
)
